# schematic.net
KiCad netlist of a schematic drawn in Altium Designer
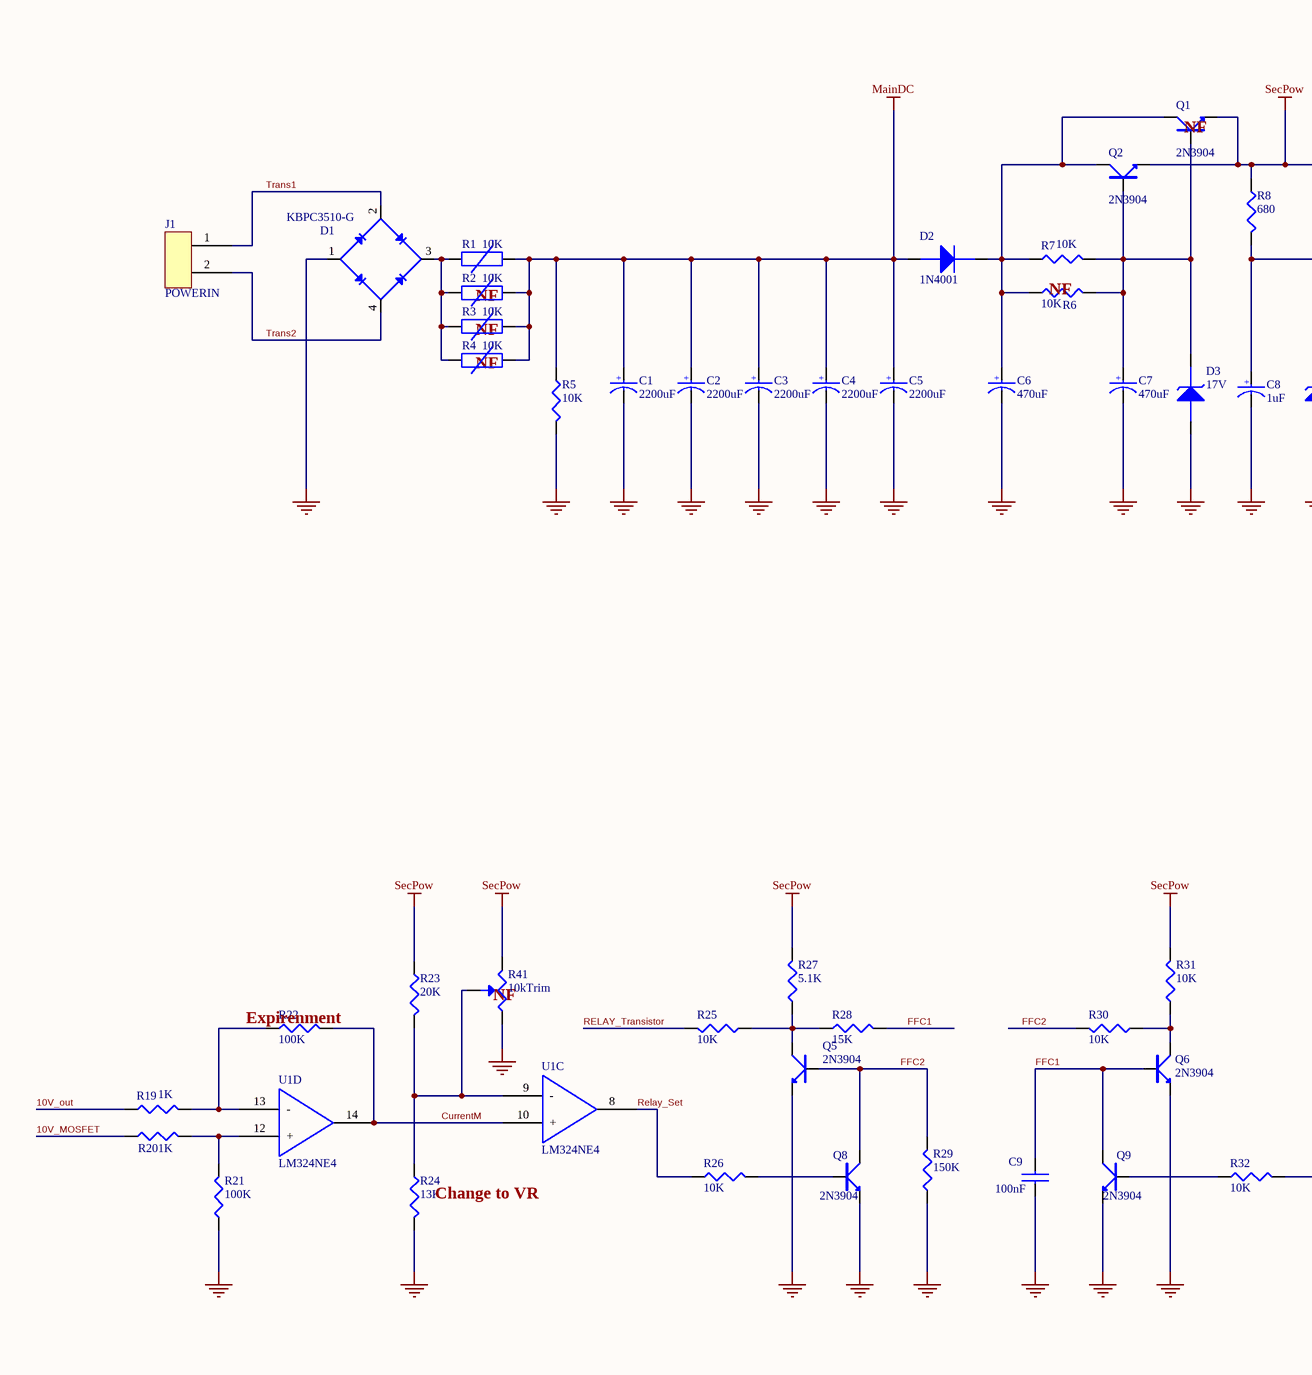
[diagram p0: schematic.SchDoc, left]
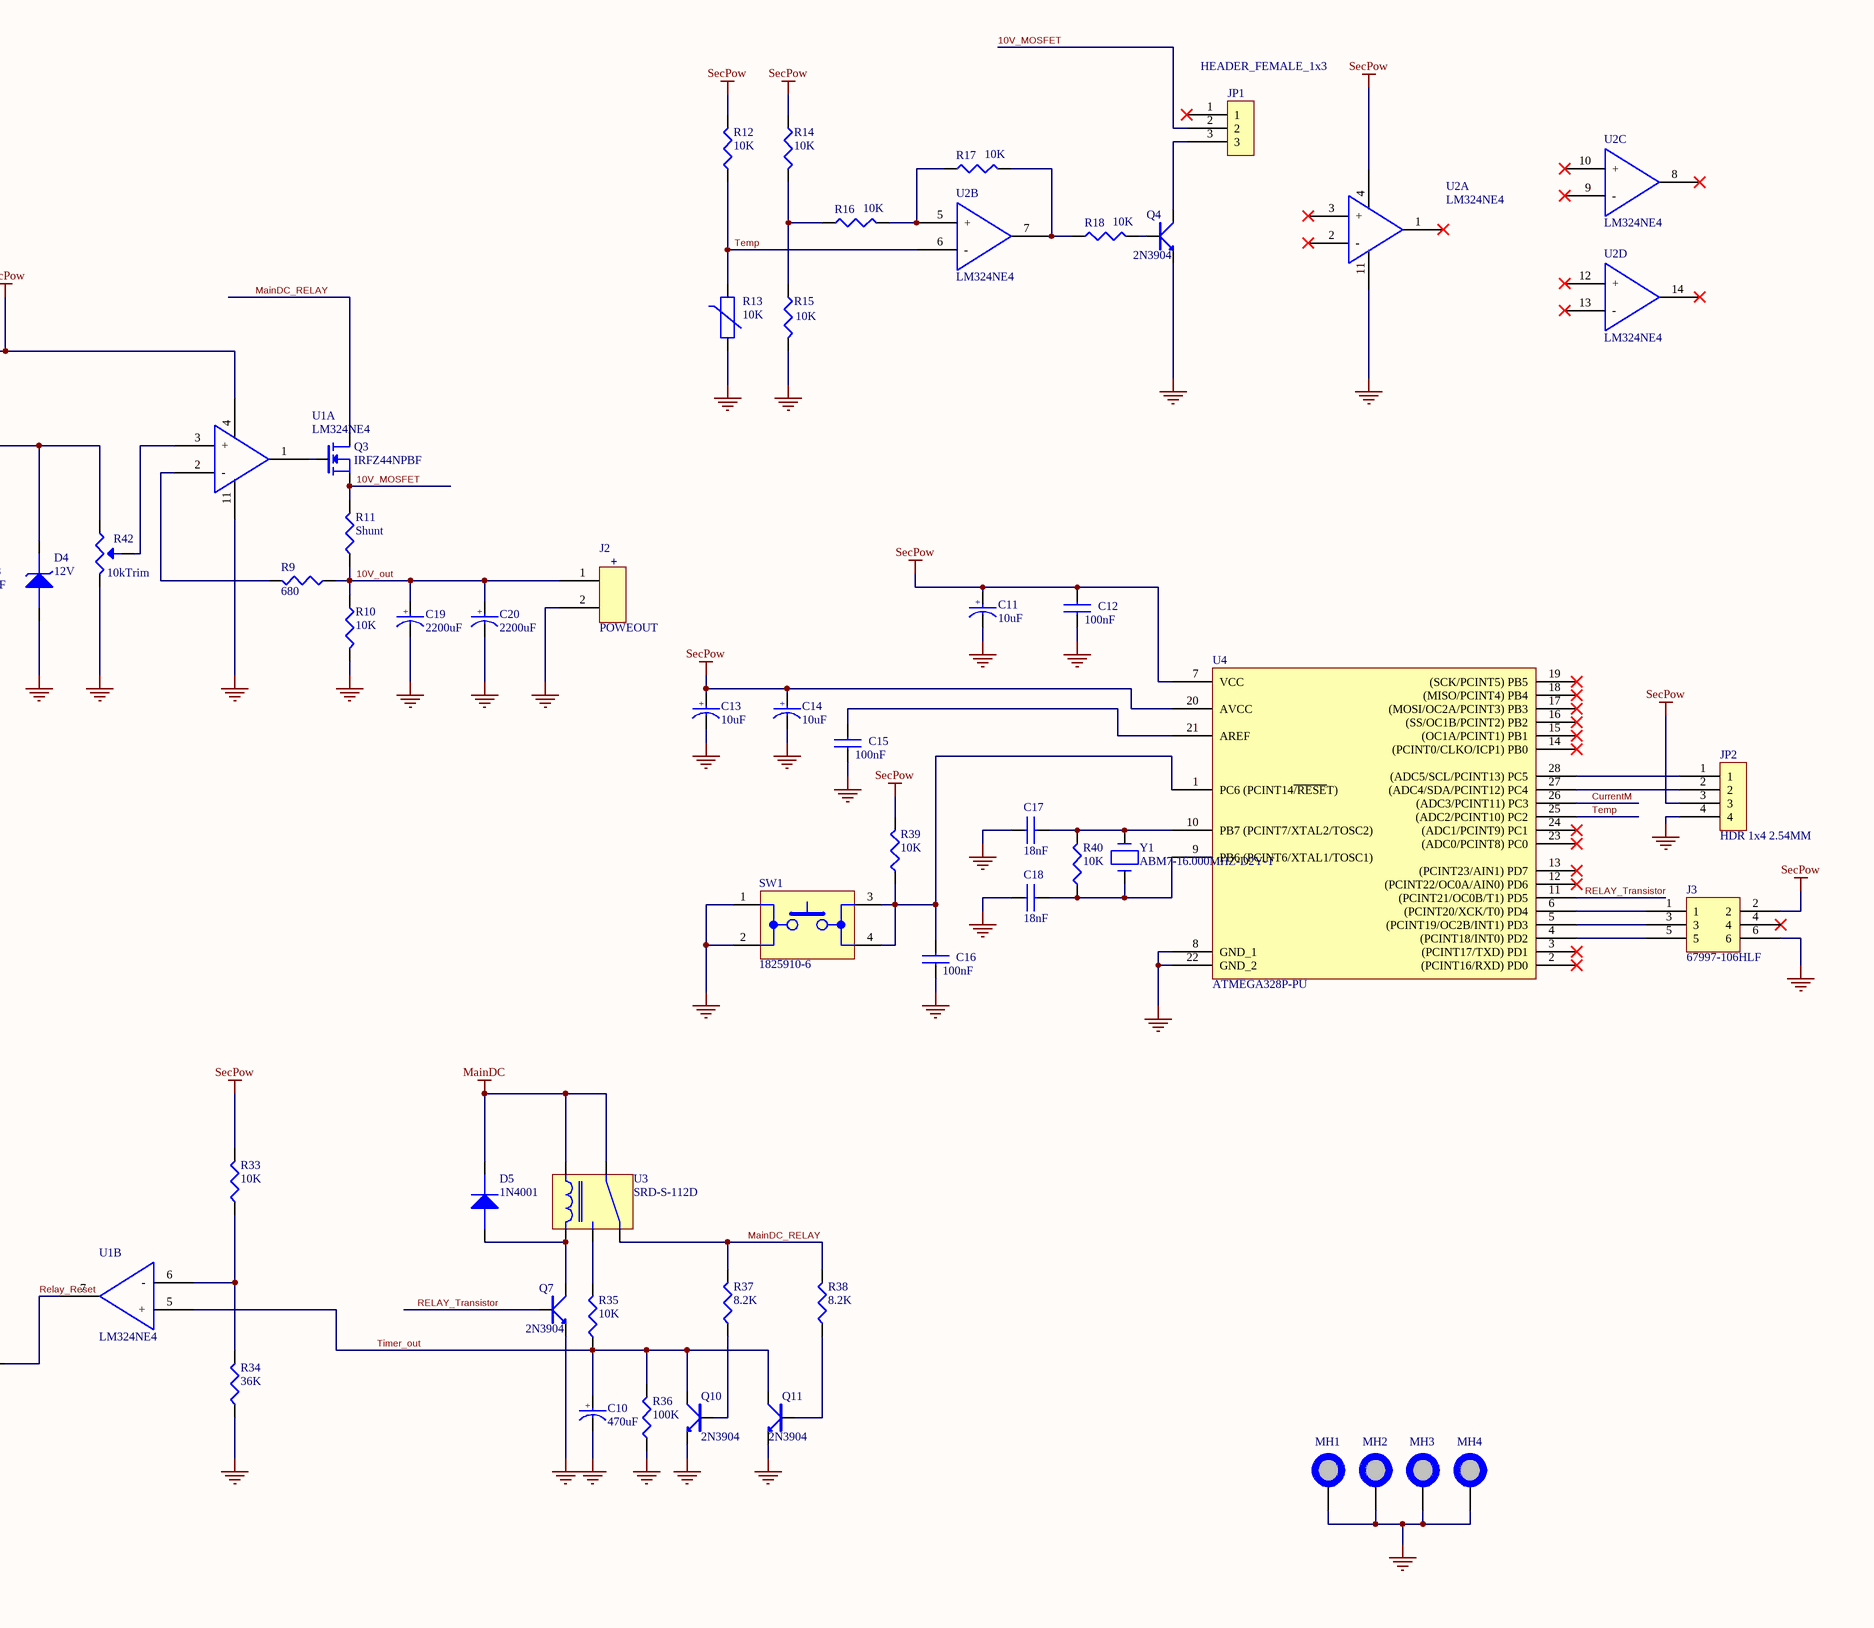
[diagram p1: schematic.SchDoc, right]

(export (version "E")
  (design (tool "Eeschema 10.0.6"))
  (components
    (comp (ref "C1")
      (value "2200uF")
      (footprint "CAP_3.5MM")
      (description "Cap Aluminum Lytic 470uF 35V 20% (12.5 X 15mm) Radial 5mm 1450mA 10000h 105 Bulk")
      (fields
        (field (name "MANUFACTURER") "Nichicon")
        (field (name "MANUFACTURER PART NUMBER") "UHE1V471MHD6")
      )
      (libsource (lib "ThroughHoleYSK") (part "UHE1V471MHD6"))
    )
    (comp (ref "C2")
      (value "2200uF")
      (footprint "CAP_3.5MM")
      (description "Cap Aluminum Lytic 470uF 35V 20% (12.5 X 15mm) Radial 5mm 1450mA 10000h 105 Bulk")
      (fields
        (field (name "MANUFACTURER") "Nichicon")
        (field (name "MANUFACTURER PART NUMBER") "UHE1V471MHD6")
      )
      (libsource (lib "ThroughHoleYSK") (part "UHE1V471MHD6"))
    )
    (comp (ref "C3")
      (value "2200uF")
      (footprint "CAP_3.5MM")
      (description "Cap Aluminum Lytic 470uF 35V 20% (12.5 X 15mm) Radial 5mm 1450mA 10000h 105 Bulk")
      (fields
        (field (name "MANUFACTURER") "Nichicon")
        (field (name "MANUFACTURER PART NUMBER") "UHE1V471MHD6")
      )
      (libsource (lib "ThroughHoleYSK") (part "UHE1V471MHD6"))
    )
    (comp (ref "C4")
      (value "2200uF")
      (footprint "CAP_3.5MM")
      (description "Cap Aluminum Lytic 470uF 35V 20% (12.5 X 15mm) Radial 5mm 1450mA 10000h 105 Bulk")
      (fields
        (field (name "MANUFACTURER") "Nichicon")
        (field (name "MANUFACTURER PART NUMBER") "UHE1V471MHD6")
      )
      (libsource (lib "ThroughHoleYSK") (part "UHE1V471MHD6"))
    )
    (comp (ref "C5")
      (value "2200uF")
      (footprint "CAP_3.5MM")
      (description "Cap Aluminum Lytic 470uF 35V 20% (12.5 X 15mm) Radial 5mm 1450mA 10000h 105 Bulk")
      (fields
        (field (name "MANUFACTURER") "Nichicon")
        (field (name "MANUFACTURER PART NUMBER") "UHE1V471MHD6")
      )
      (libsource (lib "ThroughHoleYSK") (part "UHE1V471MHD6"))
    )
    (comp (ref "C6")
      (value "470uF")
      (footprint "47uf3.5MM")
      (description "Cap Aluminum Lytic 470uF 25V 20% (12.5 X 15mm) Radial 5mm 1450mA 10000h 105 Bulk")
      (fields
        (field (name "MANUFACTURER") "Nichicon")
        (field (name "MANUFACTURER PART NUMBER") "UHE1V471MHD6")
      )
      (libsource (lib "ThroughHoleYSK") (part "47uF"))
    )
    (comp (ref "C7")
      (value "470uF")
      (footprint "47uf3.5MM")
      (description "Cap Aluminum Lytic 470uF 25V 20% (12.5 X 15mm) Radial 5mm 1450mA 10000h 105 Bulk")
      (fields
        (field (name "MANUFACTURER") "Nichicon")
        (field (name "MANUFACTURER PART NUMBER") "UHE1V471MHD6")
      )
      (libsource (lib "ThroughHoleYSK") (part "47uF"))
    )
    (comp (ref "C8")
      (value "1uF")
      (footprint "1uF2MM")
      (description "Cap Aluminum Lytic 1uF 100V 20% (12.5 X 15mm) Radial 5mm 1450mA 10000h 105 Bulk")
      (fields
        (field (name "MANUFACTURER") "Nichicon")
        (field (name "MANUFACTURER PART NUMBER") "UHE1V471MHD6")
      )
      (libsource (lib "ThroughHoleYSK") (part "1uF"))
    )
    (comp (ref "C9")
      (value "100nF")
      (footprint "100nF3MM")
      (description "Cap Aluminum Lytic 1uF 100V 20% (12.5 X 15mm) Radial 5mm 1450mA 10000h 105 Bulk")
      (fields
        (field (name "MANUFACTURER") "Nichicon")
        (field (name "MANUFACTURER PART NUMBER") "UHE1V471MHD6")
      )
      (libsource (lib "ThroughHoleYSK") (part "100nF"))
    )
    (comp (ref "C10")
      (value "470uF")
      (footprint "47uf3.5MM")
      (description "Cap Aluminum Lytic 470uF 25V 20% (12.5 X 15mm) Radial 5mm 1450mA 10000h 105 Bulk")
      (fields
        (field (name "MANUFACTURER") "Nichicon")
        (field (name "MANUFACTURER PART NUMBER") "UHE1V471MHD6")
      )
      (libsource (lib "ThroughHoleYSK") (part "47uF"))
    )
    (comp (ref "C11")
      (value "10uF")
      (footprint "1uF2MM")
      (description "Cap Aluminum Lytic 1uF 100V 20% (12.5 X 15mm) Radial 5mm 1450mA 10000h 105 Bulk")
      (fields
        (field (name "MANUFACTURER") "Nichicon")
        (field (name "MANUFACTURER PART NUMBER") "UHE1V471MHD6")
      )
      (libsource (lib "ThroughHoleYSK") (part "1uF"))
    )
    (comp (ref "C12")
      (value "100nF")
      (footprint "100nF3MM")
      (description "Cap Aluminum Lytic 1uF 100V 20% (12.5 X 15mm) Radial 5mm 1450mA 10000h 105 Bulk")
      (fields
        (field (name "MANUFACTURER") "Nichicon")
        (field (name "MANUFACTURER PART NUMBER") "UHE1V471MHD6")
      )
      (libsource (lib "ThroughHoleYSK") (part "100nF"))
    )
    (comp (ref "C13")
      (value "10uF")
      (footprint "1uF2MM")
      (description "Cap Aluminum Lytic 1uF 100V 20% (12.5 X 15mm) Radial 5mm 1450mA 10000h 105 Bulk")
      (fields
        (field (name "MANUFACTURER") "Nichicon")
        (field (name "MANUFACTURER PART NUMBER") "UHE1V471MHD6")
      )
      (libsource (lib "ThroughHoleYSK") (part "1uF"))
    )
    (comp (ref "C14")
      (value "10uF")
      (footprint "1uF2MM")
      (description "Cap Aluminum Lytic 1uF 100V 20% (12.5 X 15mm) Radial 5mm 1450mA 10000h 105 Bulk")
      (fields
        (field (name "MANUFACTURER") "Nichicon")
        (field (name "MANUFACTURER PART NUMBER") "UHE1V471MHD6")
      )
      (libsource (lib "ThroughHoleYSK") (part "1uF"))
    )
    (comp (ref "C15")
      (value "100nF")
      (footprint "100nF3MM")
      (description "Cap Aluminum Lytic 1uF 100V 20% (12.5 X 15mm) Radial 5mm 1450mA 10000h 105 Bulk")
      (fields
        (field (name "MANUFACTURER") "Nichicon")
        (field (name "MANUFACTURER PART NUMBER") "UHE1V471MHD6")
      )
      (libsource (lib "ThroughHoleYSK") (part "100nF"))
    )
    (comp (ref "C16")
      (value "100nF")
      (footprint "100nF3MM")
      (description "Cap Aluminum Lytic 1uF 100V 20% (12.5 X 15mm) Radial 5mm 1450mA 10000h 105 Bulk")
      (fields
        (field (name "MANUFACTURER") "Nichicon")
        (field (name "MANUFACTURER PART NUMBER") "UHE1V471MHD6")
      )
      (libsource (lib "ThroughHoleYSK") (part "100nF"))
    )
    (comp (ref "C17")
      (value "18nF")
      (footprint "100nF3MM")
      (description "Cap Aluminum Lytic 1uF 100V 20% (12.5 X 15mm) Radial 5mm 1450mA 10000h 105 Bulk")
      (fields
        (field (name "MANUFACTURER") "Nichicon")
        (field (name "MANUFACTURER PART NUMBER") "UHE1V471MHD6")
      )
      (libsource (lib "ThroughHoleYSK") (part "100nF"))
    )
    (comp (ref "C18")
      (value "18nF")
      (footprint "100nF3MM")
      (description "Cap Aluminum Lytic 1uF 100V 20% (12.5 X 15mm) Radial 5mm 1450mA 10000h 105 Bulk")
      (fields
        (field (name "MANUFACTURER") "Nichicon")
        (field (name "MANUFACTURER PART NUMBER") "UHE1V471MHD6")
      )
      (libsource (lib "ThroughHoleYSK") (part "100nF"))
    )
    (comp (ref "C19")
      (value "2200uF")
      (footprint "CAP_3.5MM")
      (description "Cap Aluminum Lytic 470uF 35V 20% (12.5 X 15mm) Radial 5mm 1450mA 10000h 105 Bulk")
      (fields
        (field (name "MANUFACTURER") "Nichicon")
        (field (name "MANUFACTURER PART NUMBER") "UHE1V471MHD6")
      )
      (libsource (lib "ThroughHoleYSK") (part "UHE1V471MHD6"))
    )
    (comp (ref "C20")
      (value "2200uF")
      (footprint "CAP_3.5MM")
      (description "Cap Aluminum Lytic 470uF 35V 20% (12.5 X 15mm) Radial 5mm 1450mA 10000h 105 Bulk")
      (fields
        (field (name "MANUFACTURER") "Nichicon")
        (field (name "MANUFACTURER PART NUMBER") "UHE1V471MHD6")
      )
      (libsource (lib "ThroughHoleYSK") (part "UHE1V471MHD6"))
    )
    (comp (ref "D1")
      (value "KBPC3510-G")
      (footprint "RECTIFIER")
      (description "Rectifier Bridge Diode Single 1KV 35A 4-Pin Case KBPC Box")
      (fields (field (name "MANUFACTURER") "Comchip"))
      (libsource (lib "ThroughHoleYSK") (part "KBPC3510-G"))
    )
    (comp (ref "D2")
      (value "1N4001")
      (footprint "1N4001")
      (description "Rectifier Diode, 1 Element, 1A, 50V V(RRM), Silicon, DO-41")
      (fields (field (name "MANUFACTURER") "ON Semiconductor / Fairchild"))
      (libsource (lib "ThroughHoleYSK") (part "1N4001"))
    )
    (comp (ref "D3")
      (value "17V")
      (footprint "1N4001")
      (description "Zener Diode, 1 Element, 1A, 50V V(RRM), Silicon, DO-41")
      (fields
        (field (name "MANUFACTURER") "ON Semiconductor / Fairchild")
        (field (name "MANUFACTURER PART NUMBER") "1N4001")
      )
      (libsource (lib "ThroughHoleYSK") (part "17v_zener"))
    )
    (comp (ref "D4")
      (value "12V")
      (footprint "1N4001")
      (description "Zener Diode, 1 Element, 1A, 50V V(RRM), Silicon, DO-41")
      (fields
        (field (name "MANUFACTURER") "ON Semiconductor / Fairchild")
        (field (name "MANUFACTURER PART NUMBER") "1N4001")
      )
      (libsource (lib "ThroughHoleYSK") (part "17v_zener"))
    )
    (comp (ref "D5")
      (value "1N4001")
      (footprint "1N4001")
      (description "Rectifier Diode, 1 Element, 1A, 50V V(RRM), Silicon, DO-41")
      (fields (field (name "MANUFACTURER") "ON Semiconductor / Fairchild"))
      (libsource (lib "ThroughHoleYSK") (part "1N4001"))
    )
    (comp (ref "J1")
      (value "POWERIN")
      (footprint "TR_CONN")
      (description "Connector for transformer")
      (fields (field (name "MANUFACTURER") "Comchip") (field (name "MANUFACTURER PART NUMBER") "KBPC3510-G"))
      (libsource (lib "ThroughHoleYSK") (part "TransformerConn"))
    )
    (comp (ref "J2")
      (value "POWEOUT")
      (footprint "Output")
      (description "Connector for PowrOut")
      (fields (field (name "MANUFACTURER") "Comchip") (field (name "MANUFACTURER PART NUMBER") "KBPC3510-G"))
      (libsource (lib "ThroughHoleYSK") (part "OUTPUT"))
    )
    (comp (ref "J3")
      (value "67997-106HLF")
      (footprint "HDR_2x3_2.54MM")
      (description "Conn Unshrouded Header HDR 6 POS 2.54mm Solder ST Top Entry Thru-Hole BergStik® Bulk")
      (fields (field (name "MANUFACTURER") "ICC"))
      (libsource (lib "ThroughHoleYSK") (part "67997-106HLF"))
    )
    (comp (ref "JP1")
      (value "HEADER_FEMALE_1x3")
      (footprint "HDR_1x3_2.54MM")
      (description "Conn Unshrouded Header HDR 3 POS 2.54mm Solder ST Top Entry Thru-Hole BergStik® Automotive Bulk")
      (fields
        (field (name "MANUFACTURER") "Amphenol ICC")
        (field (name "MANUFACTURER PART NUMBER") "68000-103HLF")
      )
      (libsource (lib "ThroughHoleYSK") (part "68000-103HLF"))
    )
    (comp (ref "JP2")
      (value "HDR 1x4 2.54MM")
      (footprint "MALEHEADER_1x4_2.54MM")
      (description "Conn Unshrouded Header HDR 4 POS 2.54mm Solder ST Thru-Hole Bag")
      (fields
        (field (name "MANUFACTURER") "Amphenol ICC / FCI")
        (field (name "MANUFACTURER PART NUMBER") "68001-204HLF")
      )
      (libsource (lib "ThroughHoleYSK") (part "68001-204HLF"))
    )
    (comp (ref "MH1")
      (value "Mounting_hole_17.4_3.2")
      (footprint "MH_17.4_3.2")
      (description "Mounting Hole plated")
      (libsource (lib "ThroughHoleYSK") (part "Mounting_hole_17.4_3.2"))
    )
    (comp (ref "MH2")
      (value "Mounting_hole_17.4_3.2")
      (footprint "MH_17.4_3.2")
      (description "Mounting Hole plated")
      (libsource (lib "ThroughHoleYSK") (part "Mounting_hole_17.4_3.2"))
    )
    (comp (ref "MH3")
      (value "Mounting_hole_17.4_3.2")
      (footprint "MH_17.4_3.2")
      (description "Mounting Hole plated")
      (libsource (lib "ThroughHoleYSK") (part "Mounting_hole_17.4_3.2"))
    )
    (comp (ref "MH4")
      (value "Mounting_hole_17.4_3.2")
      (footprint "MH_17.4_3.2")
      (description "Mounting Hole plated")
      (libsource (lib "ThroughHoleYSK") (part "Mounting_hole_17.4_3.2"))
    )
    (comp (ref "Q1")
      (value "2N3904")
      (footprint "2N3904")
      (description "Bipolar Transistor, TO-92, 40V, 200mA, NPN")
      (fields (field (name "MANUFACTURER") "ON Semiconductor / Fairchild"))
      (libsource (lib "ThroughHoleYSK") (part "2N3904"))
    )
    (comp (ref "Q2")
      (value "2N3904")
      (footprint "2N3904")
      (description "Bipolar Transistor, TO-92, 40V, 200mA, NPN")
      (fields (field (name "MANUFACTURER") "ON Semiconductor / Fairchild"))
      (libsource (lib "ThroughHoleYSK") (part "2N3904"))
    )
    (comp (ref "Q3")
      (value "IRFZ44NPBF")
      (footprint "IRFZ44N")
      (description "MOSFET, Power; N-Ch; VDSS 55V; RDS(ON) 17.5 Milliohms; ID 49A; TO-220AB; PD 94W; -55deg")
      (fields (field (name "MANUFACTURER") "International Rectifier"))
      (libsource (lib "ThroughHoleYSK") (part "IRFZ44NPBF"))
    )
    (comp (ref "Q4")
      (value "2N3904")
      (footprint "2N3904")
      (description "Bipolar Transistor, TO-92, 40V, 200mA, NPN")
      (fields (field (name "MANUFACTURER") "ON Semiconductor / Fairchild"))
      (libsource (lib "ThroughHoleYSK") (part "2N3904"))
    )
    (comp (ref "Q5")
      (value "2N3904")
      (footprint "2N3904")
      (description "Bipolar Transistor, TO-92, 40V, 200mA, NPN")
      (fields (field (name "MANUFACTURER") "ON Semiconductor / Fairchild"))
      (libsource (lib "ThroughHoleYSK") (part "2N3904"))
    )
    (comp (ref "Q6")
      (value "2N3904")
      (footprint "2N3904")
      (description "Bipolar Transistor, TO-92, 40V, 200mA, NPN")
      (fields (field (name "MANUFACTURER") "ON Semiconductor / Fairchild"))
      (libsource (lib "ThroughHoleYSK") (part "2N3904"))
    )
    (comp (ref "Q7")
      (value "2N3904")
      (footprint "2N3904")
      (description "Bipolar Transistor, TO-92, 40V, 200mA, NPN")
      (fields (field (name "MANUFACTURER") "ON Semiconductor / Fairchild"))
      (libsource (lib "ThroughHoleYSK") (part "2N3904"))
    )
    (comp (ref "Q8")
      (value "2N3904")
      (footprint "2N3904")
      (description "Bipolar Transistor, TO-92, 40V, 200mA, NPN")
      (fields (field (name "MANUFACTURER") "ON Semiconductor / Fairchild"))
      (libsource (lib "ThroughHoleYSK") (part "2N3904"))
    )
    (comp (ref "Q9")
      (value "2N3904")
      (footprint "2N3904")
      (description "Bipolar Transistor, TO-92, 40V, 200mA, NPN")
      (fields (field (name "MANUFACTURER") "ON Semiconductor / Fairchild"))
      (libsource (lib "ThroughHoleYSK") (part "2N3904"))
    )
    (comp (ref "Q10")
      (value "2N3904")
      (footprint "2N3904")
      (description "Bipolar Transistor, TO-92, 40V, 200mA, NPN")
      (fields (field (name "MANUFACTURER") "ON Semiconductor / Fairchild"))
      (libsource (lib "ThroughHoleYSK") (part "2N3904"))
    )
    (comp (ref "Q11")
      (value "2N3904")
      (footprint "2N3904")
      (description "Bipolar Transistor, TO-92, 40V, 200mA, NPN")
      (fields (field (name "MANUFACTURER") "ON Semiconductor / Fairchild"))
      (libsource (lib "ThroughHoleYSK") (part "2N3904"))
    )
    (comp (ref "R1")
      (value "10K")
      (footprint "Thermistor")
      (description "Thermistor")
      (fields
        (field (name "MANUFACTURER") "Yageo")
        (field (name "MANUFACTURER PART NUMBER") "MFR-25FBF52-1K")
      )
      (libsource (lib "ThroughHoleYSK") (part "Thermister_10K"))
    )
    (comp (ref "R2")
      (value "10K")
      (footprint "Thermistor")
      (description "Thermistor")
      (fields
        (field (name "MANUFACTURER") "Yageo")
        (field (name "MANUFACTURER PART NUMBER") "MFR-25FBF52-1K")
      )
      (libsource (lib "ThroughHoleYSK") (part "Thermister_10K"))
    )
    (comp (ref "R3")
      (value "10K")
      (footprint "Thermistor")
      (description "Thermistor")
      (fields
        (field (name "MANUFACTURER") "Yageo")
        (field (name "MANUFACTURER PART NUMBER") "MFR-25FBF52-1K")
      )
      (libsource (lib "ThroughHoleYSK") (part "Thermister_10K"))
    )
    (comp (ref "R4")
      (value "10K")
      (footprint "Thermistor")
      (description "Thermistor")
      (fields
        (field (name "MANUFACTURER") "Yageo")
        (field (name "MANUFACTURER PART NUMBER") "MFR-25FBF52-1K")
      )
      (libsource (lib "ThroughHoleYSK") (part "Thermister_10K"))
    )
    (comp (ref "R5")
      (value "10K")
      (footprint "RES_0.25W")
      (description "Res Metal Film 10K Ohm 1% 1/4W ±100ppm/°C Conformal Axial Thru-Hole T/R")
      (fields
        (field (name "MANUFACTURER") "Yageo")
        (field (name "MANUFACTURER PART NUMBER") "MFR-25FRF52-10K")
      )
      (libsource (lib "ThroughHoleYSK") (part "MFR-25FRF52-10K"))
    )
    (comp (ref "R6")
      (value "10K")
      (footprint "RES_0.25W")
      (description "Res Metal Film 10K Ohm 1% 1/4W ±100ppm/°C Conformal Axial Thru-Hole T/R")
      (fields
        (field (name "MANUFACTURER") "Yageo")
        (field (name "MANUFACTURER PART NUMBER") "MFR-25FRF52-10K")
      )
      (libsource (lib "ThroughHoleYSK") (part "MFR-25FRF52-10K"))
    )
    (comp (ref "R7")
      (value "10K")
      (footprint "RES_0.25W")
      (description "Res Metal Film 10K Ohm 1% 1/4W ±100ppm/°C Conformal Axial Thru-Hole T/R")
      (fields
        (field (name "MANUFACTURER") "Yageo")
        (field (name "MANUFACTURER PART NUMBER") "MFR-25FRF52-10K")
      )
      (libsource (lib "ThroughHoleYSK") (part "MFR-25FRF52-10K"))
    )
    (comp (ref "R8")
      (value "680")
      (footprint "RES_0.25W")
      (description "Res Metal Film 680Ohm 1% 1/4W ±100ppm/°C Conformal Axial Thru-Hole T/R")
      (fields
        (field (name "MANUFACTURER") "Yageo")
        (field (name "MANUFACTURER PART NUMBER") "MFR-25FRF52-10K")
      )
      (libsource (lib "ThroughHoleYSK") (part "MFR-25FRF52-10K"))
    )
    (comp (ref "R9")
      (value "680")
      (footprint "RES_0.25W")
      (description "Res Metal Film 680Ohm 1% 1/4W ±100ppm/°C Conformal Axial Thru-Hole T/R")
      (fields
        (field (name "MANUFACTURER") "Yageo")
        (field (name "MANUFACTURER PART NUMBER") "MFR-25FRF52-10K")
      )
      (libsource (lib "ThroughHoleYSK") (part "MFR-25FRF52-10K"))
    )
    (comp (ref "R10")
      (value "10K")
      (footprint "RES_0.25W")
      (description "Res Metal Film 10K Ohm 1% 1/4W ±100ppm/°C Conformal Axial Thru-Hole T/R")
      (fields
        (field (name "MANUFACTURER") "Yageo")
        (field (name "MANUFACTURER PART NUMBER") "MFR-25FRF52-10K")
      )
      (libsource (lib "ThroughHoleYSK") (part "MFR-25FRF52-10K"))
    )
    (comp (ref "R11")
      (value "Shunt")
      (footprint "shunt")
      (fields
        (field (name "MANUFACTURER") "Yageo")
        (field (name "MANUFACTURER PART NUMBER") "MFR-25FTE52-36K")
        (field (name "TOLERANCE") "1%")
      )
      (libsource (lib "ThroughHoleYSK") (part "Shunt"))
    )
    (comp (ref "R12")
      (value "10K")
      (footprint "RES_0.25W")
      (description "Res Metal Film 10K Ohm 1% 1/4W ±100ppm/°C Conformal Axial Thru-Hole T/R")
      (fields
        (field (name "MANUFACTURER") "Yageo")
        (field (name "MANUFACTURER PART NUMBER") "MFR-25FRF52-10K")
      )
      (libsource (lib "ThroughHoleYSK") (part "MFR-25FRF52-10K"))
    )
    (comp (ref "R13")
      (value "10K")
      (footprint "Thermistor")
      (description "Thermistor")
      (fields
        (field (name "MANUFACTURER") "Yageo")
        (field (name "MANUFACTURER PART NUMBER") "MFR-25FBF52-1K")
      )
      (libsource (lib "ThroughHoleYSK") (part "Thermister_10K"))
    )
    (comp (ref "R14")
      (value "10K")
      (footprint "RES_0.25W")
      (description "Res Metal Film 10K Ohm 1% 1/4W ±100ppm/°C Conformal Axial Thru-Hole T/R")
      (fields
        (field (name "MANUFACTURER") "Yageo")
        (field (name "MANUFACTURER PART NUMBER") "MFR-25FRF52-10K")
      )
      (libsource (lib "ThroughHoleYSK") (part "MFR-25FRF52-10K"))
    )
    (comp (ref "R15")
      (value "10K")
      (footprint "RES_0.25W")
      (description "Res Metal Film 10K Ohm 1% 1/4W ±100ppm/°C Conformal Axial Thru-Hole T/R")
      (fields
        (field (name "MANUFACTURER") "Yageo")
        (field (name "MANUFACTURER PART NUMBER") "MFR-25FRF52-10K")
      )
      (libsource (lib "ThroughHoleYSK") (part "MFR-25FRF52-10K"))
    )
    (comp (ref "R16")
      (value "10K")
      (footprint "RES_0.25W")
      (description "Res Metal Film 10K Ohm 1% 1/4W ±100ppm/°C Conformal Axial Thru-Hole T/R")
      (fields
        (field (name "MANUFACTURER") "Yageo")
        (field (name "MANUFACTURER PART NUMBER") "MFR-25FRF52-10K")
      )
      (libsource (lib "ThroughHoleYSK") (part "MFR-25FRF52-10K"))
    )
    (comp (ref "R17")
      (value "10K")
      (footprint "RES_0.25W")
      (description "Res Metal Film 10K Ohm 1% 1/4W ±100ppm/°C Conformal Axial Thru-Hole T/R")
      (fields
        (field (name "MANUFACTURER") "Yageo")
        (field (name "MANUFACTURER PART NUMBER") "MFR-25FRF52-10K")
      )
      (libsource (lib "ThroughHoleYSK") (part "MFR-25FRF52-10K"))
    )
    (comp (ref "R18")
      (value "10K")
      (footprint "RES_0.25W")
      (description "Res Metal Film 10K Ohm 1% 1/4W ±100ppm/°C Conformal Axial Thru-Hole T/R")
      (fields
        (field (name "MANUFACTURER") "Yageo")
        (field (name "MANUFACTURER PART NUMBER") "MFR-25FRF52-10K")
      )
      (libsource (lib "ThroughHoleYSK") (part "MFR-25FRF52-10K"))
    )
    (comp (ref "R19")
      (value "1K")
      (footprint "RES_0.25W")
      (description "General Type Metal Film Resistor 1kOhm 1/4W 1% Axial Bulk")
      (fields
        (field (name "MANUFACTURER") "Yageo")
        (field (name "MANUFACTURER PART NUMBER") "MFR-25FBF52-1K")
      )
      (libsource (lib "ThroughHoleYSK") (part "MFR-25FBF52-1K"))
    )
    (comp (ref "R20")
      (value "1K")
      (footprint "RES_0.25W")
      (description "General Type Metal Film Resistor 1kOhm 1/4W 1% Axial Bulk")
      (fields
        (field (name "MANUFACTURER") "Yageo")
        (field (name "MANUFACTURER PART NUMBER") "MFR-25FBF52-1K")
      )
      (libsource (lib "ThroughHoleYSK") (part "MFR-25FBF52-1K"))
    )
    (comp (ref "R21")
      (value "100K")
      (footprint "RES_0.25W")
      (description "Res Metal Film 36K Ohm 1% 1/4W ±100ppm/°C Conformal Axial Thru-Hole T/R")
      (fields
        (field (name "MANUFACTURER") "Yageo")
        (field (name "MANUFACTURER PART NUMBER") "MFR-25FRF52-10K")
      )
      (libsource (lib "ThroughHoleYSK") (part "MFR-25FRF52-10K"))
    )
    (comp (ref "R22")
      (value "100K")
      (footprint "RES_0.25W")
      (description "Res Metal Film 36K Ohm 1% 1/4W ±100ppm/°C Conformal Axial Thru-Hole T/R")
      (fields
        (field (name "MANUFACTURER") "Yageo")
        (field (name "MANUFACTURER PART NUMBER") "MFR-25FRF52-10K")
      )
      (libsource (lib "ThroughHoleYSK") (part "MFR-25FRF52-10K"))
    )
    (comp (ref "R23")
      (value "20K")
      (footprint "RES_0.25W")
      (description "Res Metal Film 10K Ohm 1% 1/4W ±100ppm/°C Conformal Axial Thru-Hole T/R")
      (fields
        (field (name "MANUFACTURER") "Yageo")
        (field (name "MANUFACTURER PART NUMBER") "MFR-25FRF52-10K")
      )
      (libsource (lib "ThroughHoleYSK") (part "MFR-25FRF52-10K"))
    )
    (comp (ref "R24")
      (value "13K")
      (footprint "RES_0.25W")
      (description "Res Metal Film 36K Ohm 1% 1/4W ±100ppm/°C Conformal Axial Thru-Hole T/R")
      (fields
        (field (name "MANUFACTURER") "Yageo")
        (field (name "MANUFACTURER PART NUMBER") "MFR-25FRF52-10K")
      )
      (libsource (lib "ThroughHoleYSK") (part "MFR-25FRF52-10K"))
    )
    (comp (ref "R25")
      (value "10K")
      (footprint "RES_0.25W")
      (description "Res Metal Film 10K Ohm 1% 1/4W ±100ppm/°C Conformal Axial Thru-Hole T/R")
      (fields
        (field (name "MANUFACTURER") "Yageo")
        (field (name "MANUFACTURER PART NUMBER") "MFR-25FRF52-10K")
      )
      (libsource (lib "ThroughHoleYSK") (part "MFR-25FRF52-10K"))
    )
    (comp (ref "R26")
      (value "10K")
      (footprint "RES_0.25W")
      (description "Res Metal Film 10K Ohm 1% 1/4W ±100ppm/°C Conformal Axial Thru-Hole T/R")
      (fields
        (field (name "MANUFACTURER") "Yageo")
        (field (name "MANUFACTURER PART NUMBER") "MFR-25FRF52-10K")
      )
      (libsource (lib "ThroughHoleYSK") (part "MFR-25FRF52-10K"))
    )
    (comp (ref "R27")
      (value "5.1K")
      (footprint "RES_0.25W")
      (description "General Type Metal Film Resistor 5.1kOhm 1/4W 1% Axial Bulk")
      (fields
        (field (name "MANUFACTURER") "Yageo")
        (field (name "MANUFACTURER PART NUMBER") "MFR-25FBF52-5K1")
      )
      (libsource (lib "ThroughHoleYSK") (part "MFR-25FBF52-5K1"))
    )
    (comp (ref "R28")
      (value "15K")
      (footprint "RES_0.25W")
      (description "Res Metal Film 10K Ohm 1% 1/4W ±100ppm/°C Conformal Axial Thru-Hole T/R")
      (fields
        (field (name "MANUFACTURER") "Yageo")
        (field (name "MANUFACTURER PART NUMBER") "MFR-25FRF52-10K")
      )
      (libsource (lib "ThroughHoleYSK") (part "MFR-25FRF52-10K"))
    )
    (comp (ref "R29")
      (value "150K")
      (footprint "RES_0.25W")
      (description "General Type Metal Film Resistor 150kOhm 1/4W 1% Axial Bulk")
      (fields
        (field (name "MANUFACTURER") "Yageo")
        (field (name "MANUFACTURER PART NUMBER") "MFR-25FBF52-150K")
      )
      (libsource (lib "ThroughHoleYSK") (part "MFR-25FBF52-150K"))
    )
    (comp (ref "R30")
      (value "10K")
      (footprint "RES_0.25W")
      (description "Res Metal Film 10K Ohm 1% 1/4W ±100ppm/°C Conformal Axial Thru-Hole T/R")
      (fields
        (field (name "MANUFACTURER") "Yageo")
        (field (name "MANUFACTURER PART NUMBER") "MFR-25FRF52-10K")
      )
      (libsource (lib "ThroughHoleYSK") (part "MFR-25FRF52-10K"))
    )
    (comp (ref "R31")
      (value "10K")
      (footprint "RES_0.25W")
      (description "Res Metal Film 10K Ohm 1% 1/4W ±100ppm/°C Conformal Axial Thru-Hole T/R")
      (fields
        (field (name "MANUFACTURER") "Yageo")
        (field (name "MANUFACTURER PART NUMBER") "MFR-25FRF52-10K")
      )
      (libsource (lib "ThroughHoleYSK") (part "MFR-25FRF52-10K"))
    )
    (comp (ref "R32")
      (value "10K")
      (footprint "RES_0.25W")
      (description "Res Metal Film 10K Ohm 1% 1/4W ±100ppm/°C Conformal Axial Thru-Hole T/R")
      (fields
        (field (name "MANUFACTURER") "Yageo")
        (field (name "MANUFACTURER PART NUMBER") "MFR-25FRF52-10K")
      )
      (libsource (lib "ThroughHoleYSK") (part "MFR-25FRF52-10K"))
    )
    (comp (ref "R33")
      (value "10K")
      (footprint "RES_0.25W")
      (description "Res Metal Film 10K Ohm 1% 1/4W ±100ppm/°C Conformal Axial Thru-Hole T/R")
      (fields
        (field (name "MANUFACTURER") "Yageo")
        (field (name "MANUFACTURER PART NUMBER") "MFR-25FRF52-10K")
      )
      (libsource (lib "ThroughHoleYSK") (part "MFR-25FRF52-10K"))
    )
    (comp (ref "R34")
      (value "36K")
      (footprint "RES_0.25W")
      (description "Res Metal Film 36K Ohm 1% 1/4W ±100ppm/°C Conformal Axial Thru-Hole T/R")
      (fields
        (field (name "MANUFACTURER") "Yageo")
        (field (name "MANUFACTURER PART NUMBER") "MFR-25FRF52-10K")
      )
      (libsource (lib "ThroughHoleYSK") (part "MFR-25FRF52-10K"))
    )
    (comp (ref "R35")
      (value "10K")
      (footprint "RES_0.25W")
      (description "Res Metal Film 10K Ohm 1% 1/4W ±100ppm/°C Conformal Axial Thru-Hole T/R")
      (fields
        (field (name "MANUFACTURER") "Yageo")
        (field (name "MANUFACTURER PART NUMBER") "MFR-25FRF52-10K")
      )
      (libsource (lib "ThroughHoleYSK") (part "MFR-25FRF52-10K"))
    )
    (comp (ref "R36")
      (value "100K")
      (footprint "RES_0.25W")
      (description "Res General Purpose Metal Film 100k Ohm 1% 1/4W ±100ppm/°C Conformal Axial Bulk")
      (fields
        (field (name "MANUFACTURER") "Yageo")
        (field (name "MANUFACTURER PART NUMBER") "MFR-25FBF52-100K")
      )
      (libsource (lib "ThroughHoleYSK") (part "MFR-25FBF52-100K"))
    )
    (comp (ref "R37")
      (value "8.2K")
      (footprint "RES_0.25W")
      (description "General Type Metal Film Resistor 1kOhm 1/4W 1% Axial Bulk")
      (fields
        (field (name "MANUFACTURER") "Yageo")
        (field (name "MANUFACTURER PART NUMBER") "MFR-25FBF52-1K")
      )
      (libsource (lib "ThroughHoleYSK") (part "MFR-25FBF52-1K"))
    )
    (comp (ref "R38")
      (value "8.2K")
      (footprint "RES_0.25W")
      (description "General Type Metal Film Resistor 1kOhm 1/4W 1% Axial Bulk")
      (fields
        (field (name "MANUFACTURER") "Yageo")
        (field (name "MANUFACTURER PART NUMBER") "MFR-25FBF52-1K")
      )
      (libsource (lib "ThroughHoleYSK") (part "MFR-25FBF52-1K"))
    )
    (comp (ref "R39")
      (value "10K")
      (footprint "RES_0.25W")
      (description "Res Metal Film 10K Ohm 1% 1/4W ±100ppm/°C Conformal Axial Thru-Hole T/R")
      (fields
        (field (name "MANUFACTURER") "Yageo")
        (field (name "MANUFACTURER PART NUMBER") "MFR-25FRF52-10K")
      )
      (libsource (lib "ThroughHoleYSK") (part "MFR-25FRF52-10K"))
    )
    (comp (ref "R40")
      (value "10K")
      (footprint "RES_0.25W")
      (description "Res Metal Film 10K Ohm 1% 1/4W ±100ppm/°C Conformal Axial Thru-Hole T/R")
      (fields
        (field (name "MANUFACTURER") "Yageo")
        (field (name "MANUFACTURER PART NUMBER") "MFR-25FRF52-10K")
      )
      (libsource (lib "ThroughHoleYSK") (part "MFR-25FRF52-10K"))
    )
    (comp (ref "R41")
      (value "10kTrim")
      (footprint "TRIMPOT")
      (description "Res Metal Foil Trimmer 10K Ohm 5% 1/4W 21Turn Pin Thru-Hole Foam Pack/Box")
      (fields
        (field (name "MANUFACTURER") "VPG Foil Resistors")
        (field (name "MANUFACTURER PART NUMBER") "Y405310K0000J0L")
      )
      (libsource (lib "ThroughHoleYSK") (part "trimpot"))
    )
    (comp (ref "R42")
      (value "10kTrim")
      (footprint "TRIMPOT")
      (description "Res Metal Foil Trimmer 10K Ohm 5% 1/4W 21Turn Pin Thru-Hole Foam Pack/Box")
      (fields
        (field (name "MANUFACTURER") "VPG Foil Resistors")
        (field (name "MANUFACTURER PART NUMBER") "Y405310K0000J0L")
      )
      (libsource (lib "ThroughHoleYSK") (part "trimpot"))
    )
    (comp (ref "SW1")
      (value "1825910-6")
      (footprint "DIP41825910-6")
      (description "Switch Tactile OFF (ON) SPST Round Button PC Pins 0.05A 24VDC 1.57N Thru-Hole Loose")
      (fields (field (name "MANUFACTURER") "TE Connectivity Alcoswitch"))
      (libsource (lib "ThroughHoleYSK") (part "1825910-6"))
    )
    (comp (ref "U1")
      (value "LM324NE4")
      (footprint "DIP14")
      (description "4-Channel industry standard operational amplifier 14-PDIP 0 to 70")
      (fields (field (name "MANUFACTURER") "Texas Instruments"))
      (libsource (lib "ThroughHoleYSK") (part "LM324NE4"))
    )
    (comp (ref "U2")
      (value "LM324NE4")
      (footprint "DIP14")
      (description "4-Channel industry standard operational amplifier 14-PDIP 0 to 70")
      (fields (field (name "MANUFACTURER") "Texas Instruments"))
      (libsource (lib "ThroughHoleYSK") (part "LM324NE4"))
    )
    (comp (ref "U3")
      (value "SRD-S-112D")
      (footprint "RELAY_5PIN")
      (description "General Purpose Relay SPDT (1 Form C) 12VDC Coil Through Hole")
      (libsource (lib "ThroughHoleYSK") (part "SRD-S-112D"))
    )
    (comp (ref "U4")
      (value "ATMEGA328P-PU")
      (footprint "DIP28_7.62mm")
      (description "ATMEGA328P-PU; 8 bit Microcontroller AVR 20MHz 1; 32kb Flash; 2kb RAM; I2C SPI 2")
      (fields (field (name "MANUFACTURER") "Microchip / Atmel"))
      (libsource (lib "ThroughHoleYSK") (part "ATMEGA328P-PU"))
    )
    (comp (ref "Y1")
      (value "ABM7-16.000MHZ-D2Y-T")
      (footprint "Oscilator")
      (description "Crystal 16MHz ±20ppm (Tol) ±30ppm (Stability) 18pF FUND 50Ohm 2-Pin Mini-CSMD T/R")
      (fields (field (name "MANUFACTURER") "Abracon") (field (name "TOLERANCE") "20ppm"))
      (libsource (lib "ThroughHoleYSK") (part "ABM7-16.000MHZ-D2Y-T"))
    )
  )
  (nets
    (net (code "1") (name "/10V_MOSFET") (class "Default")
      (node (ref "JP1") (pin "2") (pinfunction "2_2") (pintype "passive"))
      (node (ref "Q3") (pin "3") (pinfunction "3_3") (pintype "passive"))
      (node (ref "R11") (pin "2") (pinfunction "2_2") (pintype "passive"))
      (node (ref "R20") (pin "1") (pinfunction "1_1") (pintype "passive"))
    )
    (net (code "2") (name "/10V_out") (class "Default")
      (node (ref "C19") (pin "1") (pinfunction "1_1") (pintype "passive"))
      (node (ref "C20") (pin "1") (pinfunction "1_1") (pintype "passive"))
      (node (ref "J2") (pin "1") (pinfunction "1_1") (pintype "passive"))
      (node (ref "R10") (pin "1") (pinfunction "1_1") (pintype "passive"))
      (node (ref "R11") (pin "1") (pinfunction "1_1") (pintype "passive"))
      (node (ref "R19") (pin "1") (pinfunction "1_1") (pintype "passive"))
      (node (ref "R9") (pin "1") (pinfunction "1_1") (pintype "passive"))
    )
    (net (code "3") (name "/CurrentM") (class "Default")
      (node (ref "R22") (pin "1") (pinfunction "1_1") (pintype "passive"))
      (node (ref "U1") (pin "10") (pinfunction "+_10") (pintype "passive"))
      (node (ref "U1") (pin "14") (pinfunction "1OUT_14") (pintype "passive"))
      (node (ref "U4") (pin "26") (pinfunction "(ADC3/PCINT11)_PC3_26") (pintype "passive"))
    )
    (net (code "4") (name "/FFC1") (class "Default")
      (node (ref "C9") (pin "2") (pinfunction "2_2") (pintype "passive"))
      (node (ref "Q6") (pin "2") (pinfunction "2_2") (pintype "passive"))
      (node (ref "Q9") (pin "3") (pinfunction "3_3") (pintype "passive"))
      (node (ref "R28") (pin "2") (pinfunction "2_2") (pintype "passive"))
    )
    (net (code "5") (name "/FFC2") (class "Default")
      (node (ref "Q5") (pin "2") (pinfunction "2_2") (pintype "passive"))
      (node (ref "Q8") (pin "3") (pinfunction "3_3") (pintype "passive"))
      (node (ref "R29") (pin "2") (pinfunction "2_2") (pintype "passive"))
      (node (ref "R30") (pin "2") (pinfunction "2_2") (pintype "passive"))
    )
    (net (code "6") (name "/MainDC_RELAY") (class "Default")
      (node (ref "Q3") (pin "2") (pinfunction "2_2") (pintype "passive"))
      (node (ref "R37") (pin "2") (pinfunction "2_2") (pintype "passive"))
      (node (ref "R38") (pin "2") (pinfunction "2_2") (pintype "passive"))
      (node (ref "U3") (pin "4") (pinfunction "4_4") (pintype "passive"))
    )
    (net (code "7") (name "/RELAY_Transistor") (class "Default")
      (node (ref "Q7") (pin "2") (pinfunction "2_2") (pintype "passive"))
      (node (ref "R25") (pin "2") (pinfunction "2_2") (pintype "passive"))
      (node (ref "U4") (pin "11") (pinfunction "(PCINT21/OC0B/T1)_PD5_11") (pintype "passive"))
    )
    (net (code "8") (name "/Relay_Reset") (class "Default")
      (node (ref "R32") (pin "2") (pinfunction "2_2") (pintype "passive"))
      (node (ref "U1") (pin "7") (pinfunction "OUT_7") (pintype "passive"))
    )
    (net (code "9") (name "/Relay_Set") (class "Default")
      (node (ref "R26") (pin "2") (pinfunction "2_2") (pintype "passive"))
      (node (ref "U1") (pin "8") (pinfunction "OUT_8") (pintype "passive"))
    )
    (net (code "10") (name "/Temp") (class "Default")
      (node (ref "R12") (pin "1") (pinfunction "1_1") (pintype "passive"))
      (node (ref "R13") (pin "2") (pinfunction "2_2") (pintype "passive"))
      (node (ref "U2") (pin "6") (pinfunction "-_6") (pintype "passive"))
      (node (ref "U4") (pin "25") (pinfunction "(ADC2/PCINT10)_PC2_25") (pintype "passive"))
    )
    (net (code "11") (name "/Timer_out") (class "Default")
      (node (ref "C10") (pin "1") (pinfunction "1_1") (pintype "passive"))
      (node (ref "Q10") (pin "3") (pinfunction "3_3") (pintype "passive"))
      (node (ref "Q11") (pin "3") (pinfunction "3_3") (pintype "passive"))
      (node (ref "R35") (pin "1") (pinfunction "1_1") (pintype "passive"))
      (node (ref "R36") (pin "2") (pinfunction "2_2") (pintype "passive"))
      (node (ref "U1") (pin "5") (pinfunction "+_5") (pintype "passive"))
    )
    (net (code "12") (name "/Trans1") (class "Default")
      (node (ref "D1") (pin "2") (pinfunction "2_2") (pintype "passive"))
      (node (ref "J1") (pin "1") (pinfunction "1_1") (pintype "passive"))
    )
    (net (code "13") (name "/Trans2") (class "Default")
      (node (ref "D1") (pin "4") (pinfunction "4_4") (pintype "passive"))
      (node (ref "J1") (pin "2") (pinfunction "2_2") (pintype "passive"))
    )
    (net (code "14") (name "GND") (class "Default")
      (node (ref "C1") (pin "2") (pinfunction "2_2") (pintype "passive"))
      (node (ref "C10") (pin "2") (pinfunction "2_2") (pintype "passive"))
      (node (ref "C11") (pin "2") (pinfunction "2_2") (pintype "passive"))
      (node (ref "C12") (pin "1") (pinfunction "1_1") (pintype "passive"))
      (node (ref "C13") (pin "2") (pinfunction "2_2") (pintype "passive"))
      (node (ref "C14") (pin "2") (pinfunction "2_2") (pintype "passive"))
      (node (ref "C15") (pin "1") (pinfunction "1_1") (pintype "passive"))
      (node (ref "C16") (pin "1") (pinfunction "1_1") (pintype "passive"))
      (node (ref "C17") (pin "2") (pinfunction "2_2") (pintype "passive"))
      (node (ref "C18") (pin "2") (pinfunction "2_2") (pintype "passive"))
      (node (ref "C19") (pin "2") (pinfunction "2_2") (pintype "passive"))
      (node (ref "C2") (pin "2") (pinfunction "2_2") (pintype "passive"))
      (node (ref "C20") (pin "2") (pinfunction "2_2") (pintype "passive"))
      (node (ref "C3") (pin "2") (pinfunction "2_2") (pintype "passive"))
      (node (ref "C4") (pin "2") (pinfunction "2_2") (pintype "passive"))
      (node (ref "C5") (pin "2") (pinfunction "2_2") (pintype "passive"))
      (node (ref "C6") (pin "2") (pinfunction "2_2") (pintype "passive"))
      (node (ref "C7") (pin "2") (pinfunction "2_2") (pintype "passive"))
      (node (ref "C8") (pin "2") (pinfunction "2_2") (pintype "passive"))
      (node (ref "C9") (pin "1") (pinfunction "1_1") (pintype "passive"))
      (node (ref "D1") (pin "1") (pinfunction "1_1") (pintype "passive"))
      (node (ref "D3") (pin "2") (pinfunction "An_2") (pintype "passive"))
      (node (ref "D4") (pin "2") (pinfunction "An_2") (pintype "passive"))
      (node (ref "J2") (pin "2") (pinfunction "2_2") (pintype "passive"))
      (node (ref "J3") (pin "6") (pinfunction "6_6") (pintype "passive"))
      (node (ref "JP2") (pin "4") (pinfunction "4_4") (pintype "passive"))
      (node (ref "MH1") (pin "1") (pinfunction "1_1") (pintype "passive"))
      (node (ref "MH2") (pin "1") (pinfunction "1_1") (pintype "passive"))
      (node (ref "MH3") (pin "1") (pinfunction "1_1") (pintype "passive"))
      (node (ref "MH4") (pin "1") (pinfunction "1_1") (pintype "passive"))
      (node (ref "Q10") (pin "1") (pinfunction "1_1") (pintype "passive"))
      (node (ref "Q11") (pin "1") (pinfunction "1_1") (pintype "passive"))
      (node (ref "Q4") (pin "1") (pinfunction "1_1") (pintype "passive"))
      (node (ref "Q5") (pin "1") (pinfunction "1_1") (pintype "passive"))
      (node (ref "Q6") (pin "1") (pinfunction "1_1") (pintype "passive"))
      (node (ref "Q7") (pin "1") (pinfunction "1_1") (pintype "passive"))
      (node (ref "Q8") (pin "1") (pinfunction "1_1") (pintype "passive"))
      (node (ref "Q9") (pin "1") (pinfunction "1_1") (pintype "passive"))
      (node (ref "R10") (pin "2") (pinfunction "2_2") (pintype "passive"))
      (node (ref "R13") (pin "1") (pinfunction "1_1") (pintype "passive"))
      (node (ref "R15") (pin "2") (pinfunction "2_2") (pintype "passive"))
      (node (ref "R21") (pin "2") (pinfunction "2_2") (pintype "passive"))
      (node (ref "R24") (pin "1") (pinfunction "1_1") (pintype "passive"))
      (node (ref "R29") (pin "1") (pinfunction "1_1") (pintype "passive"))
      (node (ref "R34") (pin "1") (pinfunction "1_1") (pintype "passive"))
      (node (ref "R36") (pin "1") (pinfunction "1_1") (pintype "passive"))
      (node (ref "R41") (pin "2") (pinfunction "2_2") (pintype "passive"))
      (node (ref "R42") (pin "2") (pinfunction "2_2") (pintype "passive"))
      (node (ref "R5") (pin "2") (pinfunction "2_2") (pintype "passive"))
      (node (ref "SW1") (pin "1") (pinfunction "1_1") (pintype "passive"))
      (node (ref "SW1") (pin "2") (pinfunction "2_2") (pintype "passive"))
      (node (ref "U1") (pin "11") (pinfunction "GND_11") (pintype "passive"))
      (node (ref "U2") (pin "11") (pinfunction "GND_11") (pintype "passive"))
      (node (ref "U4") (pin "22") (pinfunction "GND_2_22") (pintype "passive"))
      (node (ref "U4") (pin "8") (pinfunction "GND_1_8") (pintype "passive"))
    )
    (net (code "15") (name "MainDC") (class "Default")
      (node (ref "C1") (pin "1") (pinfunction "1_1") (pintype "passive"))
      (node (ref "C2") (pin "1") (pinfunction "1_1") (pintype "passive"))
      (node (ref "C3") (pin "1") (pinfunction "1_1") (pintype "passive"))
      (node (ref "C4") (pin "1") (pinfunction "1_1") (pintype "passive"))
      (node (ref "C5") (pin "1") (pinfunction "1_1") (pintype "passive"))
      (node (ref "D2") (pin "2") (pinfunction "An_2") (pintype "passive"))
      (node (ref "D5") (pin "1") (pinfunction "Ca_1") (pintype "passive"))
      (node (ref "R1") (pin "2") (pinfunction "2_2") (pintype "passive"))
      (node (ref "R2") (pin "2") (pinfunction "2_2") (pintype "passive"))
      (node (ref "R3") (pin "2") (pinfunction "2_2") (pintype "passive"))
      (node (ref "R4") (pin "2") (pinfunction "2_2") (pintype "passive"))
      (node (ref "R5") (pin "1") (pinfunction "1_1") (pintype "passive"))
      (node (ref "U3") (pin "1") (pinfunction "1_1") (pintype "passive"))
      (node (ref "U3") (pin "5") (pinfunction "5_5") (pintype "passive"))
    )
    (net (code "16") (name "Net-(D1-Pad3)") (class "Default")
      (node (ref "D1") (pin "3") (pinfunction "3_3") (pintype "passive"))
      (node (ref "R1") (pin "1") (pinfunction "1_1") (pintype "passive"))
      (node (ref "R2") (pin "1") (pinfunction "1_1") (pintype "passive"))
      (node (ref "R3") (pin "1") (pinfunction "1_1") (pintype "passive"))
      (node (ref "R4") (pin "1") (pinfunction "1_1") (pintype "passive"))
    )
    (net (code "17") (name "Net-(D2-Ca)") (class "Default")
      (node (ref "C6") (pin "1") (pinfunction "1_1") (pintype "passive"))
      (node (ref "D2") (pin "1") (pinfunction "Ca_1") (pintype "passive"))
      (node (ref "Q1") (pin "3") (pinfunction "3_3") (pintype "passive"))
      (node (ref "Q2") (pin "3") (pinfunction "3_3") (pintype "passive"))
      (node (ref "R6") (pin "1") (pinfunction "1_1") (pintype "passive"))
      (node (ref "R7") (pin "1") (pinfunction "1_1") (pintype "passive"))
    )
    (net (code "18") (name "Net-(D3-Ca)") (class "Default")
      (node (ref "C7") (pin "1") (pinfunction "1_1") (pintype "passive"))
      (node (ref "D3") (pin "1") (pinfunction "Ca_1") (pintype "passive"))
      (node (ref "Q1") (pin "2") (pinfunction "2_2") (pintype "passive"))
      (node (ref "Q2") (pin "2") (pinfunction "2_2") (pintype "passive"))
      (node (ref "R6") (pin "2") (pinfunction "2_2") (pintype "passive"))
      (node (ref "R7") (pin "2") (pinfunction "2_2") (pintype "passive"))
    )
    (net (code "19") (name "Net-(D4-Ca)") (class "Default")
      (node (ref "C8") (pin "1") (pinfunction "1_1") (pintype "passive"))
      (node (ref "D4") (pin "1") (pinfunction "Ca_1") (pintype "passive"))
      (node (ref "R42") (pin "3") (pinfunction "3_3") (pintype "passive"))
      (node (ref "R8") (pin "2") (pinfunction "2_2") (pintype "passive"))
    )
    (net (code "20") (name "Net-(D5-An)") (class "Default")
      (node (ref "D5") (pin "2") (pinfunction "An_2") (pintype "passive"))
      (node (ref "Q7") (pin "3") (pinfunction "3_3") (pintype "passive"))
      (node (ref "U3") (pin "2") (pinfunction "2_2") (pintype "passive"))
    )
    (net (code "21") (name "Net-(JP1-Pad3)") (class "Default")
      (node (ref "JP1") (pin "3") (pinfunction "3_3") (pintype "passive"))
      (node (ref "Q4") (pin "3") (pinfunction "3_3") (pintype "passive"))
    )
    (net (code "22") (name "Net-(Q4-Pad2)") (class "Default")
      (node (ref "Q4") (pin "2") (pinfunction "2_2") (pintype "passive"))
      (node (ref "R18") (pin "2") (pinfunction "2_2") (pintype "passive"))
    )
    (net (code "23") (name "Net-(Q5-Pad3)") (class "Default")
      (node (ref "Q5") (pin "3") (pinfunction "3_3") (pintype "passive"))
      (node (ref "R25") (pin "1") (pinfunction "1_1") (pintype "passive"))
      (node (ref "R27") (pin "1") (pinfunction "1_1") (pintype "passive"))
      (node (ref "R28") (pin "1") (pinfunction "1_1") (pintype "passive"))
    )
    (net (code "24") (name "Net-(Q6-Pad3)") (class "Default")
      (node (ref "Q6") (pin "3") (pinfunction "3_3") (pintype "passive"))
      (node (ref "R30") (pin "1") (pinfunction "1_1") (pintype "passive"))
      (node (ref "R31") (pin "1") (pinfunction "1_1") (pintype "passive"))
    )
    (net (code "25") (name "Net-(Q8-Pad2)") (class "Default")
      (node (ref "Q8") (pin "2") (pinfunction "2_2") (pintype "passive"))
      (node (ref "R26") (pin "1") (pinfunction "1_1") (pintype "passive"))
    )
    (net (code "26") (name "Net-(Q9-Pad2)") (class "Default")
      (node (ref "Q9") (pin "2") (pinfunction "2_2") (pintype "passive"))
      (node (ref "R32") (pin "1") (pinfunction "1_1") (pintype "passive"))
    )
    (net (code "27") (name "Net-(Q10-Pad2)") (class "Default")
      (node (ref "Q10") (pin "2") (pinfunction "2_2") (pintype "passive"))
      (node (ref "R37") (pin "1") (pinfunction "1_1") (pintype "passive"))
    )
    (net (code "28") (name "Net-(Q11-Pad2)") (class "Default")
      (node (ref "Q11") (pin "2") (pinfunction "2_2") (pintype "passive"))
      (node (ref "R38") (pin "1") (pinfunction "1_1") (pintype "passive"))
    )
    (net (code "29") (name "Net-(R14-Pad2)") (class "Default")
      (node (ref "R14") (pin "2") (pinfunction "2_2") (pintype "passive"))
      (node (ref "R15") (pin "1") (pinfunction "1_1") (pintype "passive"))
      (node (ref "R16") (pin "1") (pinfunction "1_1") (pintype "passive"))
    )
    (net (code "30") (name "Net-(R35-Pad2)") (class "Default")
      (node (ref "R35") (pin "2") (pinfunction "2_2") (pintype "passive"))
      (node (ref "U3") (pin "3") (pinfunction "3_3") (pintype "passive"))
    )
    (net (code "31") (name "Net-(U1A-+)") (class "Default")
      (node (ref "R42") (pin "1") (pinfunction "1_1") (pintype "passive"))
      (node (ref "U1") (pin "3") (pinfunction "+_3") (pintype "passive"))
    )
    (net (code "32") (name "Net-(U1A--)") (class "Default")
      (node (ref "R9") (pin "2") (pinfunction "2_2") (pintype "passive"))
      (node (ref "U1") (pin "2") (pinfunction "-_2") (pintype "passive"))
    )
    (net (code "33") (name "Net-(U1A-1OUT)") (class "Default")
      (node (ref "Q3") (pin "1") (pinfunction "1_1") (pintype "passive"))
      (node (ref "U1") (pin "1") (pinfunction "1OUT_1") (pintype "passive"))
    )
    (net (code "34") (name "Net-(U1B--)") (class "Default")
      (node (ref "R33") (pin "1") (pinfunction "1_1") (pintype "passive"))
      (node (ref "R34") (pin "2") (pinfunction "2_2") (pintype "passive"))
      (node (ref "U1") (pin "6") (pinfunction "-_6") (pintype "passive"))
    )
    (net (code "35") (name "Net-(U1C--)") (class "Default")
      (node (ref "R23") (pin "1") (pinfunction "1_1") (pintype "passive"))
      (node (ref "R24") (pin "2") (pinfunction "2_2") (pintype "passive"))
      (node (ref "R41") (pin "1") (pinfunction "1_1") (pintype "passive"))
      (node (ref "U1") (pin "9") (pinfunction "-_9") (pintype "passive"))
    )
    (net (code "36") (name "Net-(U1D-+)") (class "Default")
      (node (ref "R20") (pin "2") (pinfunction "2_2") (pintype "passive"))
      (node (ref "R21") (pin "1") (pinfunction "1_1") (pintype "passive"))
      (node (ref "U1") (pin "12") (pinfunction "+_12") (pintype "passive"))
    )
    (net (code "37") (name "Net-(U1D--)") (class "Default")
      (node (ref "R19") (pin "2") (pinfunction "2_2") (pintype "passive"))
      (node (ref "R22") (pin "2") (pinfunction "2_2") (pintype "passive"))
      (node (ref "U1") (pin "13") (pinfunction "-_13") (pintype "passive"))
    )
    (net (code "38") (name "Net-(U2B-+)") (class "Default")
      (node (ref "R16") (pin "2") (pinfunction "2_2") (pintype "passive"))
      (node (ref "R17") (pin "1") (pinfunction "1_1") (pintype "passive"))
      (node (ref "U2") (pin "5") (pinfunction "+_5") (pintype "passive"))
    )
    (net (code "39") (name "Net-(U2B-OUT)") (class "Default")
      (node (ref "R17") (pin "2") (pinfunction "2_2") (pintype "passive"))
      (node (ref "R18") (pin "1") (pinfunction "1_1") (pintype "passive"))
      (node (ref "U2") (pin "7") (pinfunction "OUT_7") (pintype "passive"))
    )
    (net (code "40") (name "Net-(U4-(ADC4{slash}SDA{slash}PCINT12)_PC4)") (class "Default")
      (node (ref "JP2") (pin "2") (pinfunction "2_2") (pintype "passive"))
      (node (ref "U4") (pin "27") (pinfunction "(ADC4/SDA/PCINT12)_PC4_27") (pintype "passive"))
    )
    (net (code "41") (name "Net-(U4-(ADC5{slash}SCL{slash}PCINT13)_PC5)") (class "Default")
      (node (ref "JP2") (pin "1") (pinfunction "1_1") (pintype "passive"))
      (node (ref "U4") (pin "28") (pinfunction "(ADC5/SCL/PCINT13)_PC5_28") (pintype "passive"))
    )
    (net (code "42") (name "Net-(U4-(PCINT18{slash}INT0)_PD2)") (class "Default")
      (node (ref "J3") (pin "5") (pinfunction "5_5") (pintype "passive"))
      (node (ref "U4") (pin "4") (pinfunction "(PCINT18/INT0)_PD2_4") (pintype "passive"))
    )
    (net (code "43") (name "Net-(U4-(PCINT19{slash}OC2B{slash}INT1)_PD3)") (class "Default")
      (node (ref "J3") (pin "3") (pinfunction "3_3") (pintype "passive"))
      (node (ref "U4") (pin "5") (pinfunction "(PCINT19/OC2B/INT1)_PD3_5") (pintype "passive"))
    )
    (net (code "44") (name "Net-(U4-(PCINT20{slash}XCK{slash}T0)_PD4)") (class "Default")
      (node (ref "J3") (pin "1") (pinfunction "1_1") (pintype "passive"))
      (node (ref "U4") (pin "6") (pinfunction "(PCINT20/XCK/T0)_PD4_6") (pintype "passive"))
    )
    (net (code "45") (name "Net-(U4-AREF)") (class "Default")
      (node (ref "C15") (pin "2") (pinfunction "2_2") (pintype "passive"))
      (node (ref "U4") (pin "21") (pinfunction "AREF_21") (pintype "passive"))
    )
    (net (code "46") (name "Net-(U4-PB6_(PCINT6{slash}XTAL1{slash}TOSC1))") (class "Default")
      (node (ref "C18") (pin "1") (pinfunction "1_1") (pintype "passive"))
      (node (ref "R40") (pin "1") (pinfunction "1_1") (pintype "passive"))
      (node (ref "U4") (pin "9") (pinfunction "PB6_(PCINT6/XTAL1/TOSC1)_9") (pintype "passive"))
      (node (ref "Y1") (pin "1") (pinfunction "1_1") (pintype "passive"))
    )
    (net (code "47") (name "Net-(U4-PB7_(PCINT7{slash}XTAL2{slash}TOSC2))") (class "Default")
      (node (ref "C17") (pin "1") (pinfunction "1_1") (pintype "passive"))
      (node (ref "R40") (pin "2") (pinfunction "2_2") (pintype "passive"))
      (node (ref "U4") (pin "10") (pinfunction "PB7_(PCINT7/XTAL2/TOSC2)_10") (pintype "passive"))
      (node (ref "Y1") (pin "2") (pinfunction "2_2") (pintype "passive"))
    )
    (net (code "48") (name "Net-(U4-PC6_(PCINT14~{{slash}RESE}T))") (class "Default")
      (node (ref "C16") (pin "2") (pinfunction "2_2") (pintype "passive"))
      (node (ref "R39") (pin "1") (pinfunction "1_1") (pintype "passive"))
      (node (ref "SW1") (pin "3") (pinfunction "3_3") (pintype "passive"))
      (node (ref "SW1") (pin "4") (pinfunction "4_4") (pintype "passive"))
      (node (ref "U4") (pin "1") (pinfunction "PC6_(PCINT14~{/RESE}T)_1") (pintype "passive"))
    )
    (net (code "49") (name "SecPow") (class "Default")
      (node (ref "C11") (pin "1") (pinfunction "1_1") (pintype "passive"))
      (node (ref "C12") (pin "2") (pinfunction "2_2") (pintype "passive"))
      (node (ref "C13") (pin "1") (pinfunction "1_1") (pintype "passive"))
      (node (ref "C14") (pin "1") (pinfunction "1_1") (pintype "passive"))
      (node (ref "J3") (pin "2") (pinfunction "2_2") (pintype "passive"))
      (node (ref "JP2") (pin "3") (pinfunction "3_3") (pintype "passive"))
      (node (ref "Q1") (pin "1") (pinfunction "1_1") (pintype "passive"))
      (node (ref "Q2") (pin "1") (pinfunction "1_1") (pintype "passive"))
      (node (ref "R12") (pin "2") (pinfunction "2_2") (pintype "passive"))
      (node (ref "R14") (pin "1") (pinfunction "1_1") (pintype "passive"))
      (node (ref "R23") (pin "2") (pinfunction "2_2") (pintype "passive"))
      (node (ref "R27") (pin "2") (pinfunction "2_2") (pintype "passive"))
      (node (ref "R31") (pin "2") (pinfunction "2_2") (pintype "passive"))
      (node (ref "R33") (pin "2") (pinfunction "2_2") (pintype "passive"))
      (node (ref "R39") (pin "2") (pinfunction "2_2") (pintype "passive"))
      (node (ref "R41") (pin "3") (pinfunction "3_3") (pintype "passive"))
      (node (ref "R8") (pin "1") (pinfunction "1_1") (pintype "passive"))
      (node (ref "U1") (pin "4") (pinfunction "VCC_4") (pintype "passive"))
      (node (ref "U2") (pin "4") (pinfunction "VCC_4") (pintype "passive"))
      (node (ref "U4") (pin "20") (pinfunction "AVCC_20") (pintype "passive"))
      (node (ref "U4") (pin "7") (pinfunction "VCC_7") (pintype "passive"))
    )
    (net (code "50") (name "unconnected-(J3-Pad4)") (class "Default")
      (node (ref "J3") (pin "4") (pinfunction "4_4") (pintype "passive+no_connect"))
    )
    (net (code "51") (name "unconnected-(JP1-Pad1)") (class "Default")
      (node (ref "JP1") (pin "1") (pinfunction "1_1") (pintype "passive+no_connect"))
    )
    (net (code "52") (name "unconnected-(U2A-+-Pad3)") (class "Default")
      (node (ref "U2") (pin "3") (pinfunction "+_3") (pintype "passive+no_connect"))
    )
    (net (code "53") (name "unconnected-(U2A---Pad2)") (class "Default")
      (node (ref "U2") (pin "2") (pinfunction "-_2") (pintype "passive+no_connect"))
    )
    (net (code "54") (name "unconnected-(U2A-1OUT-Pad1)") (class "Default")
      (node (ref "U2") (pin "1") (pinfunction "1OUT_1") (pintype "passive+no_connect"))
    )
    (net (code "55") (name "unconnected-(U2C-+-Pad10)") (class "Default")
      (node (ref "U2") (pin "10") (pinfunction "+_10") (pintype "passive+no_connect"))
    )
    (net (code "56") (name "unconnected-(U2C---Pad9)") (class "Default")
      (node (ref "U2") (pin "9") (pinfunction "-_9") (pintype "passive+no_connect"))
    )
    (net (code "57") (name "unconnected-(U2C-OUT-Pad8)") (class "Default")
      (node (ref "U2") (pin "8") (pinfunction "OUT_8") (pintype "passive+no_connect"))
    )
    (net (code "58") (name "unconnected-(U2D-+-Pad12)") (class "Default")
      (node (ref "U2") (pin "12") (pinfunction "+_12") (pintype "passive+no_connect"))
    )
    (net (code "59") (name "unconnected-(U2D---Pad13)") (class "Default")
      (node (ref "U2") (pin "13") (pinfunction "-_13") (pintype "passive+no_connect"))
    )
    (net (code "60") (name "unconnected-(U2D-1OUT-Pad14)") (class "Default")
      (node (ref "U2") (pin "14") (pinfunction "1OUT_14") (pintype "passive+no_connect"))
    )
    (net (code "61") (name "unconnected-(U4-(ADC0{slash}PCINT8)_PC0-Pad23)") (class "Default")
      (node (ref "U4") (pin "23") (pinfunction "(ADC0/PCINT8)_PC0_23") (pintype "passive+no_connect"))
    )
    (net (code "62") (name "unconnected-(U4-(ADC1{slash}PCINT9)_PC1-Pad24)") (class "Default")
      (node (ref "U4") (pin "24") (pinfunction "(ADC1/PCINT9)_PC1_24") (pintype "passive+no_connect"))
    )
    (net (code "63") (name "unconnected-(U4-(MISO{slash}PCINT4)_PB4-Pad18)") (class "Default")
      (node (ref "U4") (pin "18") (pinfunction "(MISO/PCINT4)_PB4_18") (pintype "passive+no_connect"))
    )
    (net (code "64") (name "unconnected-(U4-(MOSI{slash}OC2A{slash}PCINT3)_PB3-Pad17)") (class "Default")
      (node (ref "U4") (pin "17") (pinfunction "(MOSI/OC2A/PCINT3)_PB3_17") (pintype "passive+no_connect"))
    )
    (net (code "65") (name "unconnected-(U4-(OC1A{slash}PCINT1)_PB1-Pad15)") (class "Default")
      (node (ref "U4") (pin "15") (pinfunction "(OC1A/PCINT1)_PB1_15") (pintype "passive+no_connect"))
    )
    (net (code "66") (name "unconnected-(U4-(PCINT0{slash}CLKO{slash}ICP1)_PB0-Pad14)") (class "Default")
      (node (ref "U4") (pin "14") (pinfunction "(PCINT0/CLKO/ICP1)_PB0_14") (pintype "passive+no_connect"))
    )
    (net (code "67") (name "unconnected-(U4-(PCINT16{slash}RXD)_PD0-Pad2)") (class "Default")
      (node (ref "U4") (pin "2") (pinfunction "(PCINT16/RXD)_PD0_2") (pintype "passive+no_connect"))
    )
    (net (code "68") (name "unconnected-(U4-(PCINT17{slash}TXD)_PD1-Pad3)") (class "Default")
      (node (ref "U4") (pin "3") (pinfunction "(PCINT17/TXD)_PD1_3") (pintype "passive+no_connect"))
    )
    (net (code "69") (name "unconnected-(U4-(PCINT22{slash}OC0A{slash}AIN0)_PD6-Pad12)") (class "Default")
      (node (ref "U4") (pin "12") (pinfunction "(PCINT22/OC0A/AIN0)_PD6_12") (pintype "passive+no_connect"))
    )
    (net (code "70") (name "unconnected-(U4-(PCINT23{slash}AIN1)_PD7-Pad13)") (class "Default")
      (node (ref "U4") (pin "13") (pinfunction "(PCINT23/AIN1)_PD7_13") (pintype "passive+no_connect"))
    )
    (net (code "71") (name "unconnected-(U4-(SCK{slash}PCINT5)_PB5-Pad19)") (class "Default")
      (node (ref "U4") (pin "19") (pinfunction "(SCK/PCINT5)_PB5_19") (pintype "passive+no_connect"))
    )
    (net (code "72") (name "unconnected-(U4-(SS{slash}OC1B{slash}PCINT2)_PB2-Pad16)") (class "Default")
      (node (ref "U4") (pin "16") (pinfunction "(SS/OC1B/PCINT2)_PB2_16") (pintype "passive+no_connect"))
    )
  )
)
